# design.net
KiCad netlist of a schematic drawn in Altium Designer
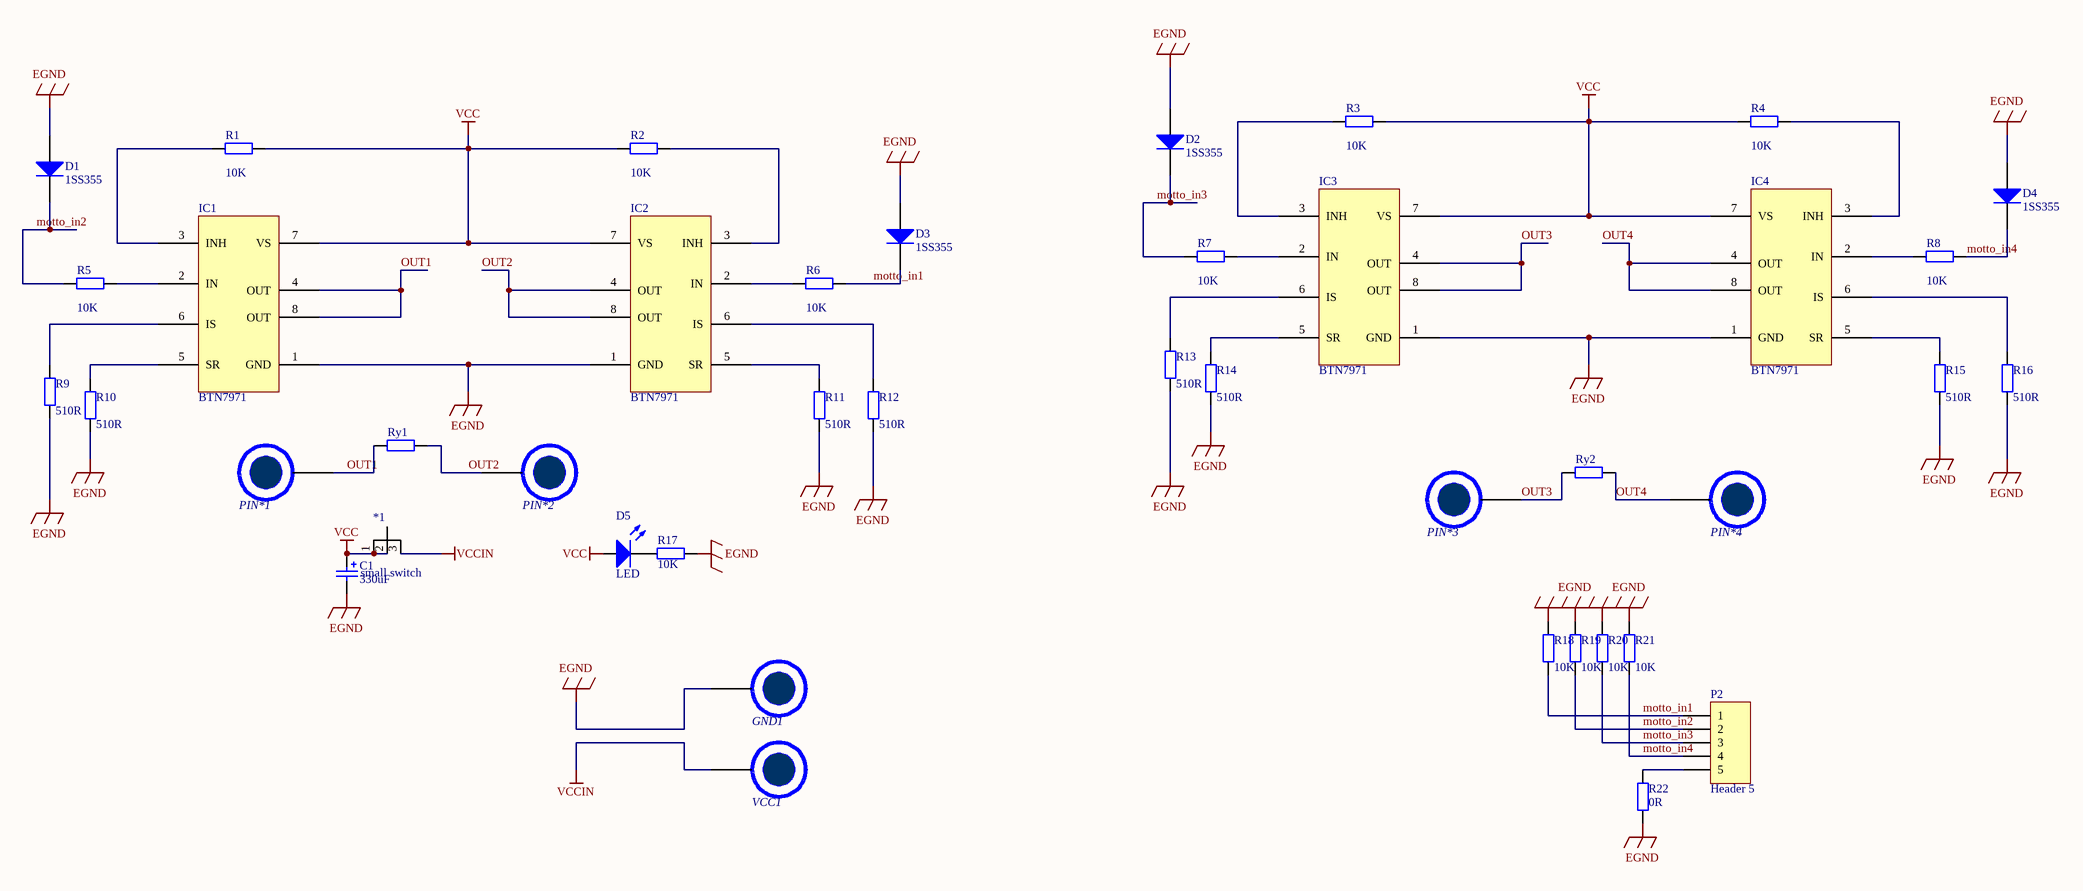
[diagram p0: 双电机驱动.SchDoc]

(export (version "E")
  (design (tool "Eeschema 10.0.6"))
  (components
    (comp (ref "*1")
      (value "small switch")
      (footprint "small switch")
      (libsource (lib "2号库") (part "small switch"))
    )
    (comp (ref "C1")
      (value "330uF")
      (footprint "SMD-EC-F12.5")
      (description "Polarized Capacitor (Radial)")
      (libsource (lib "Landzo") (part "Cap Pol1"))
    )
    (comp (ref "D1")
      (value "1SS355")
      (footprint "hole-chip diode")
      (description "High Conductance Fast Diode")
      (fields (field (name "PUBLISHER") "Altium Limited"))
      (libsource (lib "K60-V4.0") (part "Diode 1N4148"))
    )
    (comp (ref "D2")
      (value "1SS355")
      (footprint "hole-chip diode")
      (description "High Conductance Fast Diode")
      (fields (field (name "PUBLISHER") "Altium Limited"))
      (libsource (lib "K60-V4.0") (part "Diode 1N4148"))
    )
    (comp (ref "D3")
      (value "1SS355")
      (footprint "hole-chip diode")
      (description "High Conductance Fast Diode")
      (fields (field (name "PUBLISHER") "Altium Limited"))
      (libsource (lib "K60-V4.0") (part "Diode 1N4148"))
    )
    (comp (ref "D4")
      (value "1SS355")
      (footprint "hole-chip diode")
      (description "High Conductance Fast Diode")
      (fields (field (name "PUBLISHER") "Altium Limited"))
      (libsource (lib "K60-V4.0") (part "Diode 1N4148"))
    )
    (comp (ref "D5")
      (value "LED")
      (footprint "1206(2)")
      (description "Typical INFRARED GaAs LED")
      (libsource (lib "Landzo") (part "LED"))
    )
    (comp (ref "GND1") (value "PIN") (footprint "PIN") (libsource (lib "原理图") (part "PIN")))
    (comp (ref "IC1")
      (value "BTN7971")
      (footprint "PG-TO263-7-1")
      (libsource (lib "Landzo") (part "BTN7960"))
    )
    (comp (ref "IC2") (value "BTN7971") (footprint "PG-TO263-7-1") (libsource (lib "") (part "BTN7960_1")))
    (comp (ref "IC3")
      (value "BTN7971")
      (footprint "PG-TO263-7-1")
      (libsource (lib "Landzo") (part "BTN7960"))
    )
    (comp (ref "IC4") (value "BTN7971") (footprint "PG-TO263-7-1") (libsource (lib "") (part "BTN7960_1")))
    (comp (ref "P2")
      (value "Header 5")
      (footprint "HDR1X5")
      (description "Header, 5-Pin")
      (fields (field (name "PUBLISHER") "Altium Limited"))
      (libsource (lib "Sparks") (part "Header 5"))
    )
    (comp (ref "PIN*1") (value "PIN") (footprint "PIN") (libsource (lib "原理图") (part "PIN")))
    (comp (ref "PIN*2") (value "PIN") (footprint "PIN") (libsource (lib "原理图") (part "PIN")))
    (comp (ref "PIN*3") (value "PIN") (footprint "PIN") (libsource (lib "原理图") (part "PIN")))
    (comp (ref "PIN*4") (value "PIN") (footprint "PIN") (libsource (lib "原理图") (part "PIN")))
    (comp (ref "R1")
      (value "10K")
      (footprint "1206(2)")
      (description "Resistor")
      (fields (field (name "Comment") "Res2") (field (name "PUBLISHER") "Altium Limited"))
      (libsource (lib "") (part "Res2_1"))
    )
    (comp (ref "R2")
      (value "10K")
      (footprint "1206(2)")
      (description "Resistor")
      (fields (field (name "Comment") "Res2") (field (name "PUBLISHER") "Altium Limited"))
      (libsource (lib "") (part "Res2_1"))
    )
    (comp (ref "R3")
      (value "10K")
      (footprint "1206(2)")
      (description "Resistor")
      (fields (field (name "Comment") "Res2") (field (name "PUBLISHER") "Altium Limited"))
      (libsource (lib "") (part "Res2_1"))
    )
    (comp (ref "R4")
      (value "10K")
      (footprint "1206(2)")
      (description "Resistor")
      (fields (field (name "Comment") "Res2") (field (name "PUBLISHER") "Altium Limited"))
      (libsource (lib "") (part "Res2_1"))
    )
    (comp (ref "R5")
      (value "10K")
      (footprint "1206(2)")
      (description "Resistor")
      (fields (field (name "Comment") "Res2") (field (name "PUBLISHER") "Altium Limited"))
      (libsource (lib "") (part "Res2_1"))
    )
    (comp (ref "R6")
      (value "10K")
      (footprint "1206(2)")
      (description "Resistor")
      (fields (field (name "Comment") "Res2") (field (name "PUBLISHER") "Altium Limited"))
      (libsource (lib "") (part "Res2_1"))
    )
    (comp (ref "R7")
      (value "10K")
      (footprint "1206(2)")
      (description "Resistor")
      (fields (field (name "Comment") "Res2") (field (name "PUBLISHER") "Altium Limited"))
      (libsource (lib "") (part "Res2_1"))
    )
    (comp (ref "R8")
      (value "10K")
      (footprint "1206(2)")
      (description "Resistor")
      (fields (field (name "Comment") "Res2") (field (name "PUBLISHER") "Altium Limited"))
      (libsource (lib "") (part "Res2_1"))
    )
    (comp (ref "R9")
      (value "510R")
      (footprint "1206(2)")
      (description "Resistor")
      (fields (field (name "Comment") "Res2") (field (name "PUBLISHER") "Altium Limited"))
      (libsource (lib "Miscellaneous Devices") (part "Res2"))
    )
    (comp (ref "R10")
      (value "510R")
      (footprint "1206(2)")
      (description "Resistor")
      (fields (field (name "Comment") "Res2") (field (name "PUBLISHER") "Altium Limited"))
      (libsource (lib "Miscellaneous Devices") (part "Res2"))
    )
    (comp (ref "R11")
      (value "510R")
      (footprint "1206(2)")
      (description "Resistor")
      (fields (field (name "Comment") "Res2") (field (name "PUBLISHER") "Altium Limited"))
      (libsource (lib "Miscellaneous Devices") (part "Res2"))
    )
    (comp (ref "R12")
      (value "510R")
      (footprint "1206(2)")
      (description "Resistor")
      (fields (field (name "Comment") "Res2") (field (name "PUBLISHER") "Altium Limited"))
      (libsource (lib "Miscellaneous Devices") (part "Res2"))
    )
    (comp (ref "R13")
      (value "510R")
      (footprint "1206(2)")
      (description "Resistor")
      (fields (field (name "Comment") "Res2") (field (name "PUBLISHER") "Altium Limited"))
      (libsource (lib "Miscellaneous Devices") (part "Res2"))
    )
    (comp (ref "R14")
      (value "510R")
      (footprint "1206(2)")
      (description "Resistor")
      (fields (field (name "Comment") "Res2") (field (name "PUBLISHER") "Altium Limited"))
      (libsource (lib "Miscellaneous Devices") (part "Res2"))
    )
    (comp (ref "R15")
      (value "510R")
      (footprint "1206(2)")
      (description "Resistor")
      (fields (field (name "Comment") "Res2") (field (name "PUBLISHER") "Altium Limited"))
      (libsource (lib "Miscellaneous Devices") (part "Res2"))
    )
    (comp (ref "R16")
      (value "510R")
      (footprint "1206(2)")
      (description "Resistor")
      (fields (field (name "Comment") "Res2") (field (name "PUBLISHER") "Altium Limited"))
      (libsource (lib "Miscellaneous Devices") (part "Res2"))
    )
    (comp (ref "R17")
      (value "10K")
      (footprint "1206(2)")
      (description "Resistor")
      (libsource (lib "") (part "Res_1"))
    )
    (comp (ref "R18")
      (value "10K")
      (footprint "R2012")
      (description "Resistor")
      (fields (field (name "Comment") "Res2") (field (name "PUBLISHER") "Altium Limited"))
      (libsource (lib "Miscellaneous Devices") (part "Res2"))
    )
    (comp (ref "R19")
      (value "10K")
      (footprint "R2012")
      (description "Resistor")
      (fields (field (name "Comment") "Res2") (field (name "PUBLISHER") "Altium Limited"))
      (libsource (lib "Miscellaneous Devices") (part "Res2"))
    )
    (comp (ref "R20")
      (value "10K")
      (footprint "R2012")
      (description "Resistor")
      (fields (field (name "Comment") "Res2") (field (name "PUBLISHER") "Altium Limited"))
      (libsource (lib "Miscellaneous Devices") (part "Res2"))
    )
    (comp (ref "R21")
      (value "10K")
      (footprint "R2012")
      (description "Resistor")
      (fields (field (name "Comment") "Res2") (field (name "PUBLISHER") "Altium Limited"))
      (libsource (lib "Miscellaneous Devices") (part "Res2"))
    )
    (comp (ref "R22")
      (value "0R")
      (footprint "R2012")
      (description "Resistor")
      (fields (field (name "Comment") "Res2") (field (name "PUBLISHER") "Altium Limited"))
      (libsource (lib "") (part "Res2_2"))
    )
    (comp (ref "Ry1")
      (value "~")
      (footprint "1206(2)")
      (description "Resistor")
      (libsource (lib "Landzo") (part "Res"))
    )
    (comp (ref "Ry2")
      (value "~")
      (footprint "1206(2)")
      (description "Resistor")
      (libsource (lib "Landzo") (part "Res"))
    )
    (comp (ref "VCC1") (value "PIN") (footprint "PIN") (libsource (lib "原理图") (part "PIN")))
  )
  (nets
    (net (code "1") (name "/OUT1") (class "Default")
      (node (ref "IC1") (pin "4") (pinfunction "OUT_4") (pintype "passive"))
      (node (ref "IC1") (pin "8") (pinfunction "OUT_8") (pintype "passive"))
      (node (ref "PIN*1") (pin "1") (pinfunction "PIN_1") (pintype "passive"))
      (node (ref "Ry1") (pin "1") (pinfunction "1_1") (pintype "passive"))
    )
    (net (code "2") (name "/OUT2") (class "Default")
      (node (ref "IC2") (pin "4") (pinfunction "OUT_4") (pintype "passive"))
      (node (ref "IC2") (pin "8") (pinfunction "OUT_8") (pintype "passive"))
      (node (ref "PIN*2") (pin "1") (pinfunction "PIN_1") (pintype "passive"))
      (node (ref "Ry1") (pin "2") (pinfunction "2_2") (pintype "passive"))
    )
    (net (code "3") (name "/OUT3") (class "Default")
      (node (ref "IC3") (pin "4") (pinfunction "OUT_4") (pintype "passive"))
      (node (ref "IC3") (pin "8") (pinfunction "OUT_8") (pintype "passive"))
      (node (ref "PIN*3") (pin "1") (pinfunction "PIN_1") (pintype "passive"))
      (node (ref "Ry2") (pin "1") (pinfunction "1_1") (pintype "passive"))
    )
    (net (code "4") (name "/OUT4") (class "Default")
      (node (ref "IC4") (pin "4") (pinfunction "OUT_4") (pintype "passive"))
      (node (ref "IC4") (pin "8") (pinfunction "OUT_8") (pintype "passive"))
      (node (ref "PIN*4") (pin "1") (pinfunction "PIN_1") (pintype "passive"))
      (node (ref "Ry2") (pin "2") (pinfunction "2_2") (pintype "passive"))
    )
    (net (code "5") (name "/motto_in1") (class "Default")
      (node (ref "D3") (pin "2") (pinfunction "K_2") (pintype "passive"))
      (node (ref "P2") (pin "1") (pinfunction "1_1") (pintype "passive"))
      (node (ref "R18") (pin "1") (pinfunction "1_1") (pintype "passive"))
      (node (ref "R6") (pin "2") (pinfunction "2_2") (pintype "passive"))
    )
    (net (code "6") (name "/motto_in2") (class "Default")
      (node (ref "D1") (pin "2") (pinfunction "K_2") (pintype "passive"))
      (node (ref "P2") (pin "2") (pinfunction "2_2") (pintype "passive"))
      (node (ref "R19") (pin "1") (pinfunction "1_1") (pintype "passive"))
      (node (ref "R5") (pin "1") (pinfunction "1_1") (pintype "passive"))
    )
    (net (code "7") (name "/motto_in3") (class "Default")
      (node (ref "D2") (pin "2") (pinfunction "K_2") (pintype "passive"))
      (node (ref "P2") (pin "3") (pinfunction "3_3") (pintype "passive"))
      (node (ref "R20") (pin "1") (pinfunction "1_1") (pintype "passive"))
      (node (ref "R7") (pin "1") (pinfunction "1_1") (pintype "passive"))
    )
    (net (code "8") (name "/motto_in4") (class "Default")
      (node (ref "D4") (pin "2") (pinfunction "K_2") (pintype "passive"))
      (node (ref "P2") (pin "4") (pinfunction "4_4") (pintype "passive"))
      (node (ref "R21") (pin "1") (pinfunction "1_1") (pintype "passive"))
      (node (ref "R8") (pin "2") (pinfunction "2_2") (pintype "passive"))
    )
    (net (code "9") (name "EGND") (class "Default")
      (node (ref "C1") (pin "2") (pinfunction "2_2") (pintype "passive"))
      (node (ref "D1") (pin "1") (pinfunction "A_1") (pintype "passive"))
      (node (ref "D2") (pin "1") (pinfunction "A_1") (pintype "passive"))
      (node (ref "D3") (pin "1") (pinfunction "A_1") (pintype "passive"))
      (node (ref "D4") (pin "1") (pinfunction "A_1") (pintype "passive"))
      (node (ref "GND1") (pin "1") (pinfunction "PIN_1") (pintype "passive"))
      (node (ref "IC1") (pin "1") (pinfunction "GND_1") (pintype "passive"))
      (node (ref "IC2") (pin "1") (pinfunction "GND_1") (pintype "passive"))
      (node (ref "IC3") (pin "1") (pinfunction "GND_1") (pintype "passive"))
      (node (ref "IC4") (pin "1") (pinfunction "GND_1") (pintype "passive"))
      (node (ref "R10") (pin "1") (pinfunction "1_1") (pintype "passive"))
      (node (ref "R11") (pin "1") (pinfunction "1_1") (pintype "passive"))
      (node (ref "R12") (pin "1") (pinfunction "1_1") (pintype "passive"))
      (node (ref "R13") (pin "1") (pinfunction "1_1") (pintype "passive"))
      (node (ref "R14") (pin "1") (pinfunction "1_1") (pintype "passive"))
      (node (ref "R15") (pin "1") (pinfunction "1_1") (pintype "passive"))
      (node (ref "R16") (pin "1") (pinfunction "1_1") (pintype "passive"))
      (node (ref "R17") (pin "1") (pinfunction "1_1") (pintype "passive"))
      (node (ref "R18") (pin "2") (pinfunction "2_2") (pintype "passive"))
      (node (ref "R19") (pin "2") (pinfunction "2_2") (pintype "passive"))
      (node (ref "R20") (pin "2") (pinfunction "2_2") (pintype "passive"))
      (node (ref "R21") (pin "2") (pinfunction "2_2") (pintype "passive"))
      (node (ref "R22") (pin "2") (pinfunction "2_2") (pintype "passive"))
      (node (ref "R9") (pin "1") (pinfunction "1_1") (pintype "passive"))
    )
    (net (code "10") (name "Net-(D5-Pad2)") (class "Default")
      (node (ref "D5") (pin "2") (pinfunction "2_2") (pintype "passive"))
      (node (ref "R17") (pin "2") (pinfunction "2_2") (pintype "passive"))
    )
    (net (code "11") (name "Net-(IC1-IN)") (class "Default")
      (node (ref "IC1") (pin "2") (pinfunction "IN_2") (pintype "passive"))
      (node (ref "R5") (pin "2") (pinfunction "2_2") (pintype "passive"))
    )
    (net (code "12") (name "Net-(IC1-INH)") (class "Default")
      (node (ref "IC1") (pin "3") (pinfunction "INH_3") (pintype "passive"))
      (node (ref "R1") (pin "1") (pinfunction "1_1") (pintype "passive"))
    )
    (net (code "13") (name "Net-(IC1-IS)") (class "Default")
      (node (ref "IC1") (pin "6") (pinfunction "IS_6") (pintype "passive"))
      (node (ref "R9") (pin "2") (pinfunction "2_2") (pintype "passive"))
    )
    (net (code "14") (name "Net-(IC1-SR)") (class "Default")
      (node (ref "IC1") (pin "5") (pinfunction "SR_5") (pintype "passive"))
      (node (ref "R10") (pin "2") (pinfunction "2_2") (pintype "passive"))
    )
    (net (code "15") (name "Net-(IC2-IN)") (class "Default")
      (node (ref "IC2") (pin "2") (pinfunction "IN_2") (pintype "passive"))
      (node (ref "R6") (pin "1") (pinfunction "1_1") (pintype "passive"))
    )
    (net (code "16") (name "Net-(IC2-INH)") (class "Default")
      (node (ref "IC2") (pin "3") (pinfunction "INH_3") (pintype "passive"))
      (node (ref "R2") (pin "2") (pinfunction "2_2") (pintype "passive"))
    )
    (net (code "17") (name "Net-(IC2-IS)") (class "Default")
      (node (ref "IC2") (pin "6") (pinfunction "IS_6") (pintype "passive"))
      (node (ref "R12") (pin "2") (pinfunction "2_2") (pintype "passive"))
    )
    (net (code "18") (name "Net-(IC2-SR)") (class "Default")
      (node (ref "IC2") (pin "5") (pinfunction "SR_5") (pintype "passive"))
      (node (ref "R11") (pin "2") (pinfunction "2_2") (pintype "passive"))
    )
    (net (code "19") (name "Net-(IC3-IN)") (class "Default")
      (node (ref "IC3") (pin "2") (pinfunction "IN_2") (pintype "passive"))
      (node (ref "R7") (pin "2") (pinfunction "2_2") (pintype "passive"))
    )
    (net (code "20") (name "Net-(IC3-INH)") (class "Default")
      (node (ref "IC3") (pin "3") (pinfunction "INH_3") (pintype "passive"))
      (node (ref "R3") (pin "1") (pinfunction "1_1") (pintype "passive"))
    )
    (net (code "21") (name "Net-(IC3-IS)") (class "Default")
      (node (ref "IC3") (pin "6") (pinfunction "IS_6") (pintype "passive"))
      (node (ref "R13") (pin "2") (pinfunction "2_2") (pintype "passive"))
    )
    (net (code "22") (name "Net-(IC3-SR)") (class "Default")
      (node (ref "IC3") (pin "5") (pinfunction "SR_5") (pintype "passive"))
      (node (ref "R14") (pin "2") (pinfunction "2_2") (pintype "passive"))
    )
    (net (code "23") (name "Net-(IC4-IN)") (class "Default")
      (node (ref "IC4") (pin "2") (pinfunction "IN_2") (pintype "passive"))
      (node (ref "R8") (pin "1") (pinfunction "1_1") (pintype "passive"))
    )
    (net (code "24") (name "Net-(IC4-INH)") (class "Default")
      (node (ref "IC4") (pin "3") (pinfunction "INH_3") (pintype "passive"))
      (node (ref "R4") (pin "2") (pinfunction "2_2") (pintype "passive"))
    )
    (net (code "25") (name "Net-(IC4-IS)") (class "Default")
      (node (ref "IC4") (pin "6") (pinfunction "IS_6") (pintype "passive"))
      (node (ref "R16") (pin "2") (pinfunction "2_2") (pintype "passive"))
    )
    (net (code "26") (name "Net-(IC4-SR)") (class "Default")
      (node (ref "IC4") (pin "5") (pinfunction "SR_5") (pintype "passive"))
      (node (ref "R15") (pin "2") (pinfunction "2_2") (pintype "passive"))
    )
    (net (code "27") (name "Net-(P2-Pad5)") (class "Default")
      (node (ref "P2") (pin "5") (pinfunction "5_5") (pintype "passive"))
      (node (ref "R22") (pin "1") (pinfunction "1_1") (pintype "passive"))
    )
    (net (code "28") (name "VCC") (class "Default")
      (node (ref "*1") (pin "1") (pinfunction "1_1") (pintype "passive"))
      (node (ref "*1") (pin "2") (pinfunction "2_2") (pintype "passive"))
      (node (ref "C1") (pin "1") (pinfunction "1_1") (pintype "passive"))
      (node (ref "D5") (pin "1") (pinfunction "1_1") (pintype "passive"))
      (node (ref "IC1") (pin "7") (pinfunction "VS_7") (pintype "passive"))
      (node (ref "IC2") (pin "7") (pinfunction "VS_7") (pintype "passive"))
      (node (ref "IC3") (pin "7") (pinfunction "VS_7") (pintype "passive"))
      (node (ref "IC4") (pin "7") (pinfunction "VS_7") (pintype "passive"))
      (node (ref "R1") (pin "2") (pinfunction "2_2") (pintype "passive"))
      (node (ref "R2") (pin "1") (pinfunction "1_1") (pintype "passive"))
      (node (ref "R3") (pin "2") (pinfunction "2_2") (pintype "passive"))
      (node (ref "R4") (pin "1") (pinfunction "1_1") (pintype "passive"))
    )
    (net (code "29") (name "VCCIN") (class "Default")
      (node (ref "*1") (pin "3") (pinfunction "3_3") (pintype "passive"))
      (node (ref "VCC1") (pin "1") (pinfunction "PIN_1") (pintype "passive"))
    )
  )
)
